# vykonova_deska.net
KiCad netlist of a schematic drawn in EAGLE
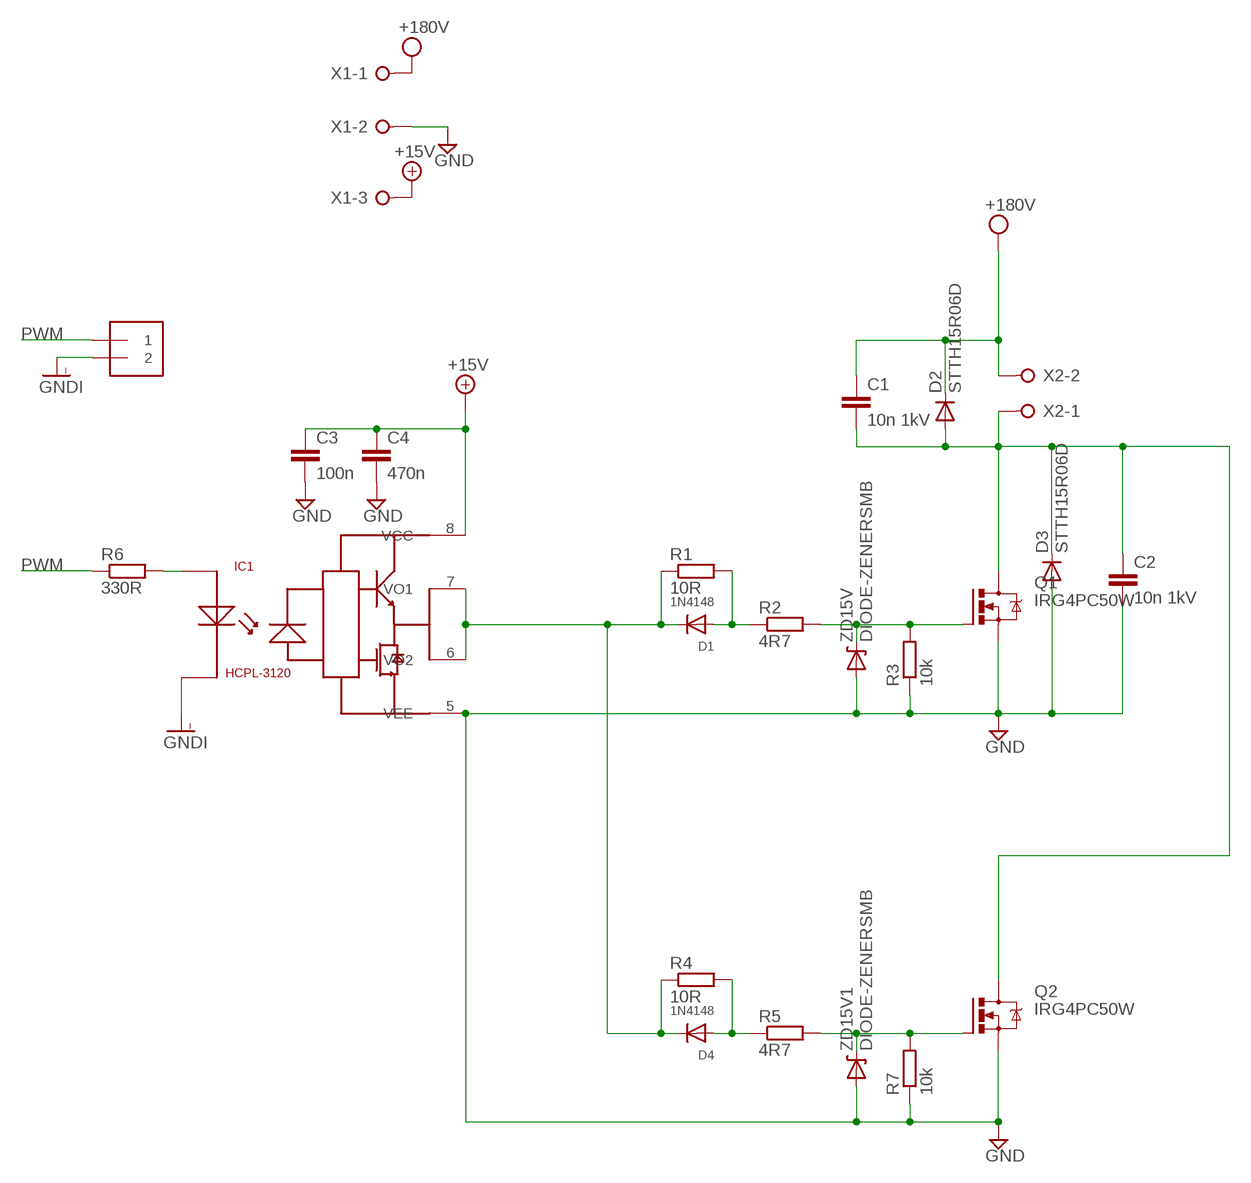
[diagram p0: schematic, sheet 1]

(export (version "E")
  (design (tool "Eeschema 10.0.6"))
  (components
    (comp (ref "C1")
      (value "10n 1kV")
      (footprint "eagle-import:C102-043X133")
      (libsource (lib "eagle-import") (part "C-EU102-043X133"))
    )
    (comp (ref "C2")
      (value "10n 1kV")
      (footprint "eagle-import:C102-043X133")
      (libsource (lib "eagle-import") (part "C-EU102-043X133"))
    )
    (comp (ref "C3")
      (value "100n")
      (footprint "eagle-import:C0603")
      (libsource (lib "eagle-import") (part "C-EUC0603"))
    )
    (comp (ref "C4")
      (value "470n")
      (footprint "eagle-import:C0603")
      (libsource (lib "eagle-import") (part "C-EUC0603"))
    )
    (comp (ref "D1")
      (value "1N4148")
      (footprint "eagle-import:SMADIODE")
      (libsource (lib "eagle-import") (part "DIODESMA"))
    )
    (comp (ref "D2")
      (value "STTH15R06D")
      (footprint "eagle-import:DO41-10")
      (libsource (lib "eagle-import") (part "1N4004"))
    )
    (comp (ref "D3")
      (value "STTH15R06D")
      (footprint "eagle-import:DO41-10")
      (libsource (lib "eagle-import") (part "1N4004"))
    )
    (comp (ref "D4")
      (value "1N4148")
      (footprint "eagle-import:SMADIODE")
      (libsource (lib "eagle-import") (part "DIODESMA"))
    )
    (comp (ref "IC1")
      (value "HCPL-3120")
      (footprint "eagle-import:DIL08-OPTO")
      (libsource (lib "eagle-import") (part "HCPL-3120"))
    )
    (comp (ref "PWM_IN")
      (value "1X2-3.5MM")
      (footprint "eagle-import:1X2-3.5MM")
      (libsource (lib "eagle-import") (part "1X2-3.5MM"))
    )
    (comp (ref "Q1")
      (value "IRG4PC50W")
      (footprint "eagle-import:TO247BV")
      (libsource (lib "eagle-import") (part "IRFPC40"))
    )
    (comp (ref "Q2")
      (value "IRG4PC50W")
      (footprint "eagle-import:TO247BV")
      (libsource (lib "eagle-import") (part "IRFPC40"))
    )
    (comp (ref "R1")
      (value "10R")
      (footprint "eagle-import:R0603")
      (libsource (lib "eagle-import") (part "R-EU_R0603"))
    )
    (comp (ref "R2")
      (value "4R7")
      (footprint "eagle-import:R0603")
      (libsource (lib "eagle-import") (part "R-EU_R0603"))
    )
    (comp (ref "R3")
      (value "10k")
      (footprint "eagle-import:R0603")
      (libsource (lib "eagle-import") (part "R-EU_R0603"))
    )
    (comp (ref "R4")
      (value "10R")
      (footprint "eagle-import:R0603")
      (libsource (lib "eagle-import") (part "R-EU_R0603"))
    )
    (comp (ref "R5")
      (value "4R7")
      (footprint "eagle-import:R0603")
      (libsource (lib "eagle-import") (part "R-EU_R0603"))
    )
    (comp (ref "R6")
      (value "330R")
      (footprint "eagle-import:R0603")
      (libsource (lib "eagle-import") (part "R-EU_R0603"))
    )
    (comp (ref "R7")
      (value "10k")
      (footprint "eagle-import:R0603")
      (libsource (lib "eagle-import") (part "R-EU_R0603"))
    )
    (comp (ref "X1")
      (value "W237-3N")
      (footprint "eagle-import:W237-3N")
      (libsource (lib "eagle-import") (part "W237-3N"))
    )
    (comp (ref "X2")
      (value "W237-2N")
      (footprint "eagle-import:W237-2N")
      (libsource (lib "eagle-import") (part "W237-2N"))
    )
    (comp (ref "ZD15V")
      (value "DIODE-ZENERSMB")
      (footprint "eagle-import:SMB-DIODE")
      (libsource (lib "eagle-import") (part "DIODE-ZENERSMB"))
    )
    (comp (ref "ZD15V1")
      (value "DIODE-ZENERSMB")
      (footprint "eagle-import:SMB-DIODE")
      (libsource (lib "eagle-import") (part "DIODE-ZENERSMB"))
    )
  )
  (nets
    (net (code "1") (name "+15V") (class "Default")
      (node (ref "C3") (pin "1") (pinfunction "1_1") (pintype "passive"))
      (node (ref "C4") (pin "1") (pinfunction "1_1") (pintype "passive"))
      (node (ref "IC1") (pin "8") (pinfunction "VCC_8") (pintype "bidirectional"))
      (node (ref "X1") (pin "3") (pinfunction "KL_3") (pintype "passive"))
    )
    (net (code "2") (name "+180V") (class "Default")
      (node (ref "C1") (pin "1") (pinfunction "1_1") (pintype "passive"))
      (node (ref "D2") (pin "C") (pinfunction "C_C") (pintype "passive"))
      (node (ref "X1") (pin "1") (pinfunction "KL_1") (pintype "passive"))
      (node (ref "X2") (pin "2") (pinfunction "KL_2") (pintype "passive"))
    )
    (net (code "3") (name "/PWM") (class "Default")
      (node (ref "PWM_IN") (pin "1") (pinfunction "1_1") (pintype "passive"))
      (node (ref "R6") (pin "1") (pinfunction "1_1") (pintype "passive"))
    )
    (net (code "4") (name "GND") (class "Default")
      (node (ref "C2") (pin "2") (pinfunction "2_2") (pintype "passive"))
      (node (ref "C3") (pin "2") (pinfunction "2_2") (pintype "passive"))
      (node (ref "C4") (pin "2") (pinfunction "2_2") (pintype "passive"))
      (node (ref "D3") (pin "A") (pinfunction "A_A") (pintype "passive"))
      (node (ref "IC1") (pin "5") (pinfunction "VEE_5") (pintype "bidirectional"))
      (node (ref "Q1") (pin "S") (pinfunction "S_S") (pintype "passive"))
      (node (ref "Q2") (pin "S") (pinfunction "S_S") (pintype "passive"))
      (node (ref "R3") (pin "1") (pinfunction "1_1") (pintype "passive"))
      (node (ref "R7") (pin "1") (pinfunction "1_1") (pintype "passive"))
      (node (ref "X1") (pin "2") (pinfunction "KL_2") (pintype "passive"))
      (node (ref "ZD15V") (pin "A") (pinfunction "A_A") (pintype "passive"))
      (node (ref "ZD15V1") (pin "A") (pinfunction "A_A") (pintype "passive"))
    )
    (net (code "5") (name "GNDI") (class "Default")
      (node (ref "IC1") (pin "3") (pinfunction "CATHODE_3") (pintype "bidirectional"))
      (node (ref "PWM_IN") (pin "2") (pinfunction "2_2") (pintype "passive"))
    )
    (net (code "6") (name "Net-(D1-PadA)") (class "Default")
      (node (ref "D1") (pin "A") (pinfunction "A_A") (pintype "passive"))
      (node (ref "R1") (pin "2") (pinfunction "2_2") (pintype "passive"))
      (node (ref "R2") (pin "1") (pinfunction "1_1") (pintype "passive"))
    )
    (net (code "7") (name "Net-(D4-PadA)") (class "Default")
      (node (ref "D4") (pin "A") (pinfunction "A_A") (pintype "passive"))
      (node (ref "R4") (pin "2") (pinfunction "2_2") (pintype "passive"))
      (node (ref "R5") (pin "1") (pinfunction "1_1") (pintype "passive"))
    )
    (net (code "8") (name "Net-(IC1-ANODE)") (class "Default")
      (node (ref "IC1") (pin "2") (pinfunction "ANODE_2") (pintype "bidirectional"))
      (node (ref "R6") (pin "2") (pinfunction "2_2") (pintype "passive"))
    )
    (net (code "9") (name "Net-(IC1-VO1)") (class "Default")
      (node (ref "D1") (pin "C") (pinfunction "C_C") (pintype "passive"))
      (node (ref "D4") (pin "C") (pinfunction "C_C") (pintype "passive"))
      (node (ref "IC1") (pin "6") (pinfunction "VO2_6") (pintype "bidirectional"))
      (node (ref "IC1") (pin "7") (pinfunction "VO1_7") (pintype "bidirectional"))
      (node (ref "R1") (pin "1") (pinfunction "1_1") (pintype "passive"))
      (node (ref "R4") (pin "1") (pinfunction "1_1") (pintype "passive"))
    )
    (net (code "10") (name "Net-(Q1-PadG)") (class "Default")
      (node (ref "Q1") (pin "G") (pinfunction "G_G") (pintype "passive"))
      (node (ref "R2") (pin "2") (pinfunction "2_2") (pintype "passive"))
      (node (ref "R3") (pin "2") (pinfunction "2_2") (pintype "passive"))
      (node (ref "ZD15V") (pin "C") (pinfunction "C_C") (pintype "passive"))
    )
    (net (code "11") (name "Net-(Q2-PadG)") (class "Default")
      (node (ref "Q2") (pin "G") (pinfunction "G_G") (pintype "passive"))
      (node (ref "R5") (pin "2") (pinfunction "2_2") (pintype "passive"))
      (node (ref "R7") (pin "2") (pinfunction "2_2") (pintype "passive"))
      (node (ref "ZD15V1") (pin "C") (pinfunction "C_C") (pintype "passive"))
    )
    (net (code "12") (name "Net-(X2A-KL)") (class "Default")
      (node (ref "C1") (pin "2") (pinfunction "2_2") (pintype "passive"))
      (node (ref "C2") (pin "1") (pinfunction "1_1") (pintype "passive"))
      (node (ref "D2") (pin "A") (pinfunction "A_A") (pintype "passive"))
      (node (ref "D3") (pin "C") (pinfunction "C_C") (pintype "passive"))
      (node (ref "Q1") (pin "D") (pinfunction "D_D") (pintype "passive"))
      (node (ref "Q2") (pin "D") (pinfunction "D_D") (pintype "passive"))
      (node (ref "X2") (pin "1") (pinfunction "KL_1") (pintype "passive"))
    )
  )
)
